# minx_ajh_1_0.net
KiCad netlist of a schematic drawn in EAGLE
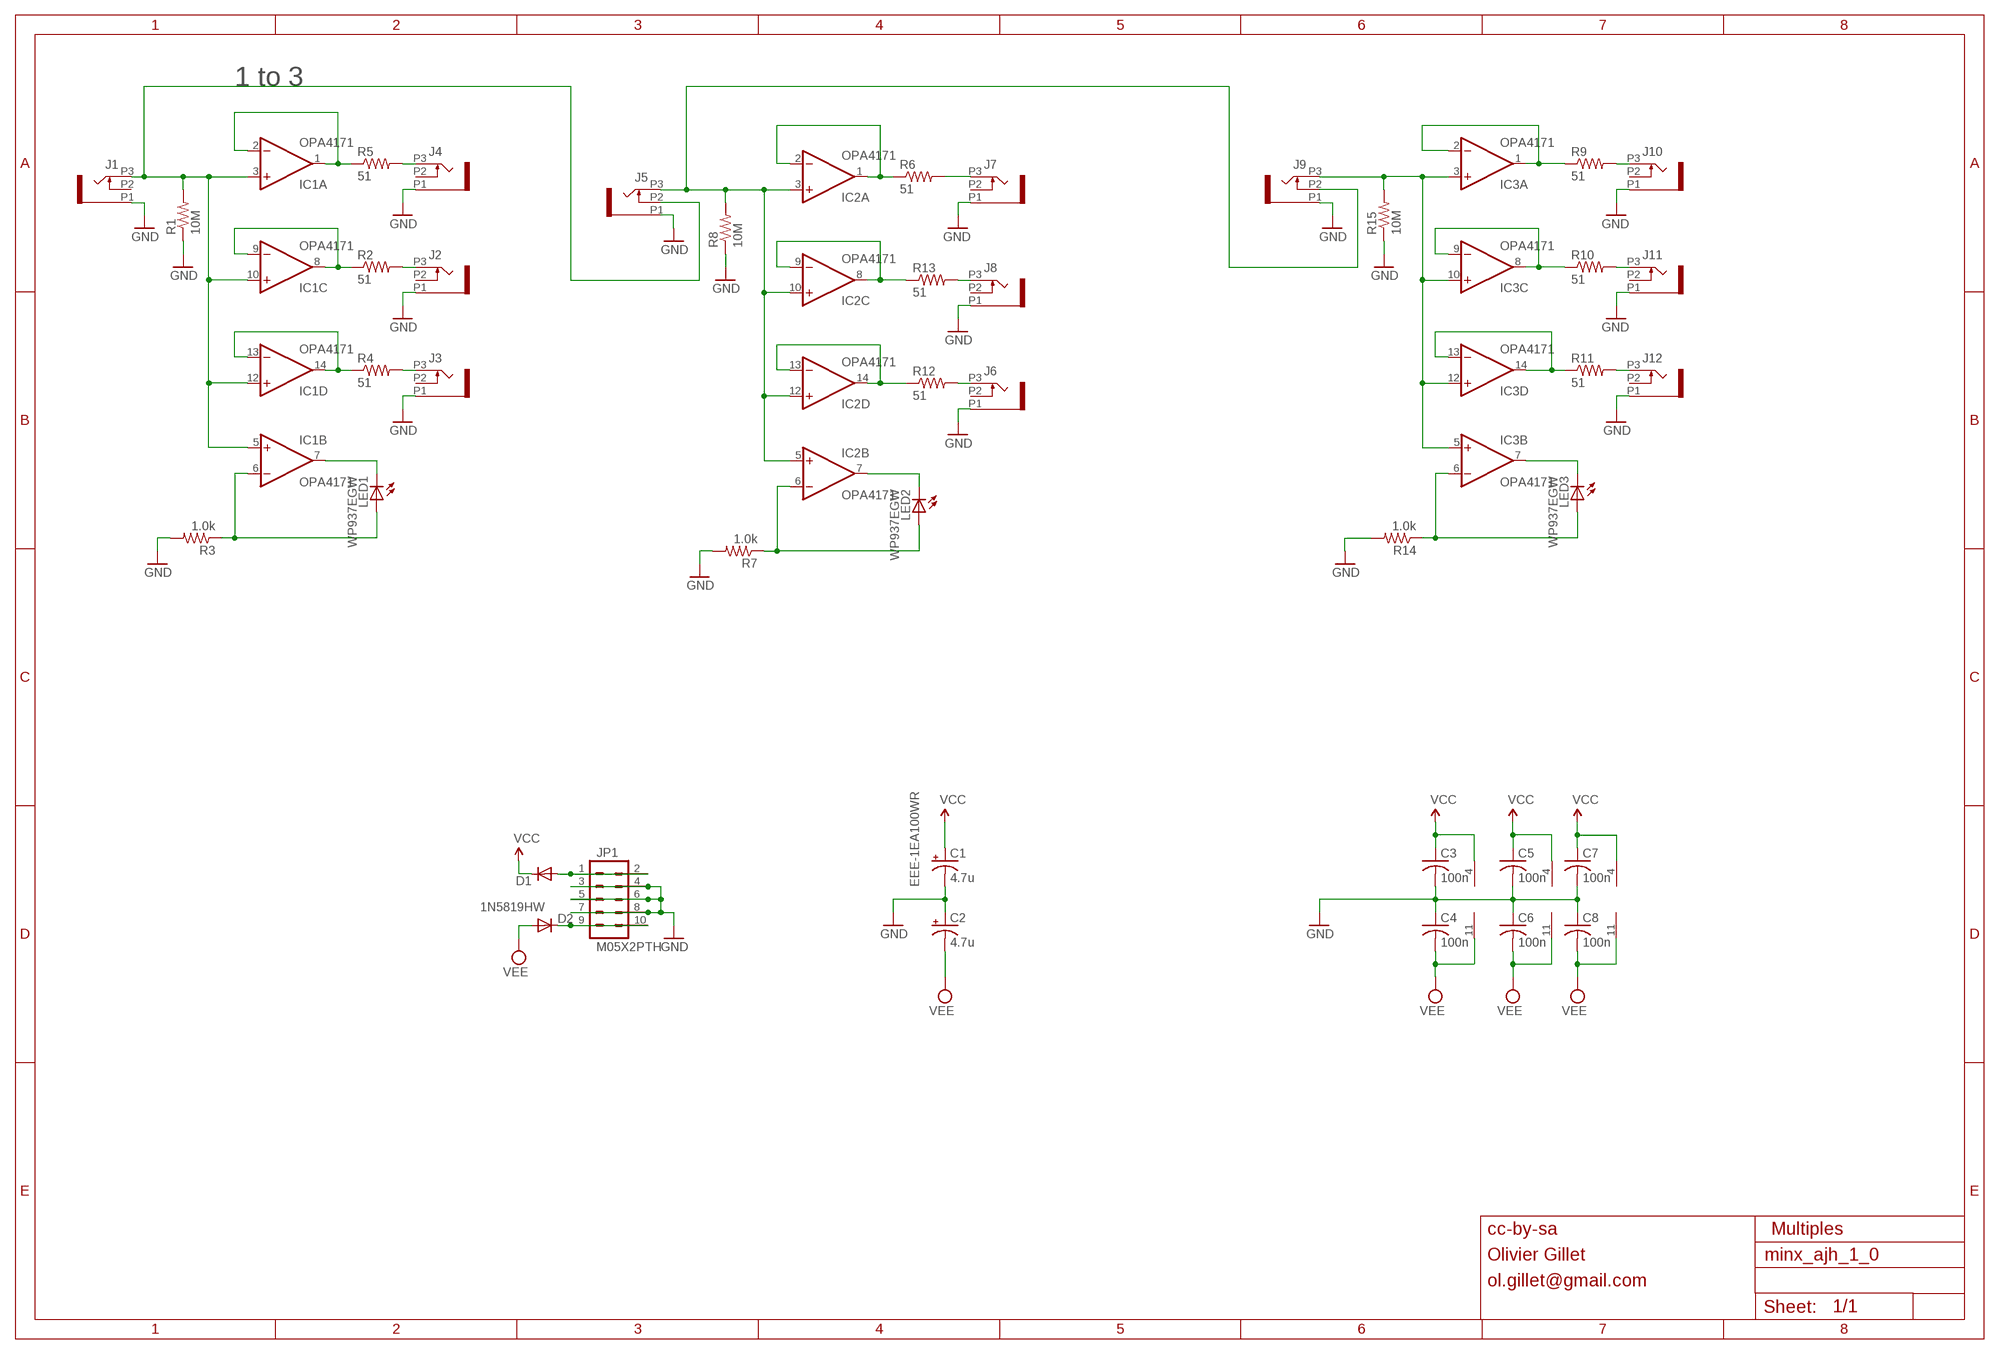
[diagram p0: schematic, sheet 1]

(export (version "E")
  (design (tool "Eeschema 10.0.6"))
  (components
    (comp (ref "C1")
      (value "4.7u")
      (footprint "eagle-import:PANASONIC_A")
      (libsource (lib "eagle-import") (part "CPOL-USA"))
    )
    (comp (ref "C2")
      (value "4.7u")
      (footprint "eagle-import:PANASONIC_A")
      (libsource (lib "eagle-import") (part "CPOL-USA"))
    )
    (comp (ref "C3")
      (value "100n")
      (footprint "eagle-import:C0603")
      (libsource (lib "eagle-import") (part "C-USC0603"))
    )
    (comp (ref "C4")
      (value "100n")
      (footprint "eagle-import:C0603")
      (libsource (lib "eagle-import") (part "C-USC0603"))
    )
    (comp (ref "C5")
      (value "100n")
      (footprint "eagle-import:C0603")
      (libsource (lib "eagle-import") (part "C-USC0603"))
    )
    (comp (ref "C6")
      (value "100n")
      (footprint "eagle-import:C0603")
      (libsource (lib "eagle-import") (part "C-USC0603"))
    )
    (comp (ref "C7")
      (value "100n")
      (footprint "eagle-import:C0603")
      (libsource (lib "eagle-import") (part "C-USC0603"))
    )
    (comp (ref "C8")
      (value "100n")
      (footprint "eagle-import:C0603")
      (libsource (lib "eagle-import") (part "C-USC0603"))
    )
    (comp (ref "D1")
      (value "1N5819HW")
      (footprint "eagle-import:SOD123")
      (libsource (lib "eagle-import") (part "DIODE-SOD123"))
    )
    (comp (ref "D2")
      (value "1N5819HW")
      (footprint "eagle-import:SOD123")
      (libsource (lib "eagle-import") (part "DIODE-SOD123"))
    )
    (comp (ref "IC1")
      (value "OPA4171")
      (footprint "eagle-import:TSSOP14")
      (libsource (lib "eagle-import") (part "TL074PW"))
    )
    (comp (ref "IC2")
      (value "OPA4171")
      (footprint "eagle-import:TSSOP14")
      (libsource (lib "eagle-import") (part "TL074PW"))
    )
    (comp (ref "IC3")
      (value "OPA4171")
      (footprint "eagle-import:TSSOP14")
      (libsource (lib "eagle-import") (part "TL074PW"))
    )
    (comp (ref "J1")
      (value "PJ301_THONKICONN6")
      (footprint "eagle-import:WQP_PJ_301M6")
      (libsource (lib "eagle-import") (part "PJ301_THONKICONN6"))
    )
    (comp (ref "J2")
      (value "PJ301_THONKICONN6")
      (footprint "eagle-import:WQP_PJ_301M6")
      (libsource (lib "eagle-import") (part "PJ301_THONKICONN6"))
    )
    (comp (ref "J3")
      (value "PJ301_THONKICONN6")
      (footprint "eagle-import:WQP_PJ_301M6")
      (libsource (lib "eagle-import") (part "PJ301_THONKICONN6"))
    )
    (comp (ref "J4")
      (value "PJ301_THONKICONN6")
      (footprint "eagle-import:WQP_PJ_301M6")
      (libsource (lib "eagle-import") (part "PJ301_THONKICONN6"))
    )
    (comp (ref "J5")
      (value "PJ301_THONKICONN6")
      (footprint "eagle-import:WQP_PJ_301M6")
      (libsource (lib "eagle-import") (part "PJ301_THONKICONN6"))
    )
    (comp (ref "J6")
      (value "PJ301_THONKICONN6")
      (footprint "eagle-import:WQP_PJ_301M6")
      (libsource (lib "eagle-import") (part "PJ301_THONKICONN6"))
    )
    (comp (ref "J7")
      (value "PJ301_THONKICONN6")
      (footprint "eagle-import:WQP_PJ_301M6")
      (libsource (lib "eagle-import") (part "PJ301_THONKICONN6"))
    )
    (comp (ref "J8")
      (value "PJ301_THONKICONN6")
      (footprint "eagle-import:WQP_PJ_301M6")
      (libsource (lib "eagle-import") (part "PJ301_THONKICONN6"))
    )
    (comp (ref "J9")
      (value "PJ301_THONKICONN6")
      (footprint "eagle-import:WQP_PJ_301M6")
      (libsource (lib "eagle-import") (part "PJ301_THONKICONN6"))
    )
    (comp (ref "J10")
      (value "PJ301_THONKICONN6")
      (footprint "eagle-import:WQP_PJ_301M6")
      (libsource (lib "eagle-import") (part "PJ301_THONKICONN6"))
    )
    (comp (ref "J11")
      (value "PJ301_THONKICONN6")
      (footprint "eagle-import:WQP_PJ_301M6")
      (libsource (lib "eagle-import") (part "PJ301_THONKICONN6"))
    )
    (comp (ref "J12")
      (value "PJ301_THONKICONN6")
      (footprint "eagle-import:WQP_PJ_301M6")
      (libsource (lib "eagle-import") (part "PJ301_THONKICONN6"))
    )
    (comp (ref "JP1")
      (value "M05X2PTH")
      (footprint "eagle-import:AVR_ICSP")
      (libsource (lib "eagle-import") (part "M05X2PTH"))
    )
    (comp (ref "LED1")
      (value "WP937EGW")
      (footprint "eagle-import:LED3MM")
      (libsource (lib "eagle-import") (part "LED3MM"))
    )
    (comp (ref "LED2")
      (value "WP937EGW")
      (footprint "eagle-import:LED3MM")
      (libsource (lib "eagle-import") (part "LED3MM"))
    )
    (comp (ref "LED3")
      (value "WP937EGW")
      (footprint "eagle-import:LED3MM")
      (libsource (lib "eagle-import") (part "LED3MM"))
    )
    (comp (ref "R1")
      (value "10M")
      (footprint "eagle-import:R0603")
      (libsource (lib "eagle-import") (part "R-US_R0603"))
    )
    (comp (ref "R2")
      (value "51")
      (footprint "eagle-import:R0603")
      (libsource (lib "eagle-import") (part "R-US_R0603"))
    )
    (comp (ref "R3")
      (value "1.0k")
      (footprint "eagle-import:R0603")
      (libsource (lib "eagle-import") (part "R-US_R0603"))
    )
    (comp (ref "R4")
      (value "51")
      (footprint "eagle-import:R0603")
      (libsource (lib "eagle-import") (part "R-US_R0603"))
    )
    (comp (ref "R5")
      (value "51")
      (footprint "eagle-import:R0603")
      (libsource (lib "eagle-import") (part "R-US_R0603"))
    )
    (comp (ref "R6")
      (value "51")
      (footprint "eagle-import:R0603")
      (libsource (lib "eagle-import") (part "R-US_R0603"))
    )
    (comp (ref "R7")
      (value "1.0k")
      (footprint "eagle-import:R0603")
      (libsource (lib "eagle-import") (part "R-US_R0603"))
    )
    (comp (ref "R8")
      (value "10M")
      (footprint "eagle-import:R0603")
      (libsource (lib "eagle-import") (part "R-US_R0603"))
    )
    (comp (ref "R9")
      (value "51")
      (footprint "eagle-import:R0603")
      (libsource (lib "eagle-import") (part "R-US_R0603"))
    )
    (comp (ref "R10")
      (value "51")
      (footprint "eagle-import:R0603")
      (libsource (lib "eagle-import") (part "R-US_R0603"))
    )
    (comp (ref "R11")
      (value "51")
      (footprint "eagle-import:R0603")
      (libsource (lib "eagle-import") (part "R-US_R0603"))
    )
    (comp (ref "R12")
      (value "51")
      (footprint "eagle-import:R0603")
      (libsource (lib "eagle-import") (part "R-US_R0603"))
    )
    (comp (ref "R13")
      (value "51")
      (footprint "eagle-import:R0603")
      (libsource (lib "eagle-import") (part "R-US_R0603"))
    )
    (comp (ref "R14")
      (value "1.0k")
      (footprint "eagle-import:R0603")
      (libsource (lib "eagle-import") (part "R-US_R0603"))
    )
    (comp (ref "R15")
      (value "10M")
      (footprint "eagle-import:R0603")
      (libsource (lib "eagle-import") (part "R-US_R0603"))
    )
  )
  (nets
    (net (code "1") (name "GND") (class "Default")
      (node (ref "C1") (pin "-") (pinfunction "-_-") (pintype "passive"))
      (node (ref "C2") (pin "+") (pinfunction "+_+") (pintype "passive"))
      (node (ref "C3") (pin "2") (pinfunction "2_2") (pintype "passive"))
      (node (ref "C4") (pin "1") (pinfunction "1_1") (pintype "passive"))
      (node (ref "C5") (pin "2") (pinfunction "2_2") (pintype "passive"))
      (node (ref "C6") (pin "1") (pinfunction "1_1") (pintype "passive"))
      (node (ref "C7") (pin "2") (pinfunction "2_2") (pintype "passive"))
      (node (ref "C8") (pin "1") (pinfunction "1_1") (pintype "passive"))
      (node (ref "J1") (pin "P1") (pinfunction "1_P1") (pintype "passive"))
      (node (ref "J10") (pin "P1") (pinfunction "1_P1") (pintype "passive"))
      (node (ref "J11") (pin "P1") (pinfunction "1_P1") (pintype "passive"))
      (node (ref "J12") (pin "P1") (pinfunction "1_P1") (pintype "passive"))
      (node (ref "J2") (pin "P1") (pinfunction "1_P1") (pintype "passive"))
      (node (ref "J3") (pin "P1") (pinfunction "1_P1") (pintype "passive"))
      (node (ref "J4") (pin "P1") (pinfunction "1_P1") (pintype "passive"))
      (node (ref "J5") (pin "P1") (pinfunction "1_P1") (pintype "passive"))
      (node (ref "J6") (pin "P1") (pinfunction "1_P1") (pintype "passive"))
      (node (ref "J7") (pin "P1") (pinfunction "1_P1") (pintype "passive"))
      (node (ref "J8") (pin "P1") (pinfunction "1_P1") (pintype "passive"))
      (node (ref "J9") (pin "P1") (pinfunction "1_P1") (pintype "passive"))
      (node (ref "JP1") (pin "3") (pinfunction "3_3") (pintype "passive"))
      (node (ref "JP1") (pin "4") (pinfunction "4_4") (pintype "passive"))
      (node (ref "JP1") (pin "5") (pinfunction "5_5") (pintype "passive"))
      (node (ref "JP1") (pin "6") (pinfunction "6_6") (pintype "passive"))
      (node (ref "JP1") (pin "7") (pinfunction "7_7") (pintype "passive"))
      (node (ref "JP1") (pin "8") (pinfunction "8_8") (pintype "passive"))
      (node (ref "R1") (pin "1") (pinfunction "1_1") (pintype "passive"))
      (node (ref "R14") (pin "2") (pinfunction "2_2") (pintype "passive"))
      (node (ref "R15") (pin "1") (pinfunction "1_1") (pintype "passive"))
      (node (ref "R3") (pin "2") (pinfunction "2_2") (pintype "passive"))
      (node (ref "R7") (pin "2") (pinfunction "2_2") (pintype "passive"))
      (node (ref "R8") (pin "1") (pinfunction "1_1") (pintype "passive"))
    )
    (net (code "2") (name "Net-(D1-PadA)") (class "Default")
      (node (ref "D1") (pin "A") (pinfunction "A_A") (pintype "passive"))
      (node (ref "JP1") (pin "1") (pinfunction "1_1") (pintype "passive"))
      (node (ref "JP1") (pin "2") (pinfunction "2_2") (pintype "passive"))
    )
    (net (code "3") (name "Net-(D2-PadC)") (class "Default")
      (node (ref "D2") (pin "C") (pinfunction "C_C") (pintype "passive"))
      (node (ref "JP1") (pin "10") (pinfunction "10_10") (pintype "passive"))
      (node (ref "JP1") (pin "9") (pinfunction "9_9") (pintype "passive"))
    )
    (net (code "4") (name "Net-(IC1A-+IN)") (class "Default")
      (node (ref "IC1") (pin "10") (pinfunction "+IN_10") (pintype "input"))
      (node (ref "IC1") (pin "12") (pinfunction "+IN_12") (pintype "input"))
      (node (ref "IC1") (pin "3") (pinfunction "+IN_3") (pintype "input"))
      (node (ref "IC1") (pin "5") (pinfunction "+IN_5") (pintype "input"))
      (node (ref "J1") (pin "P3") (pinfunction "3_P3") (pintype "passive"))
      (node (ref "J5") (pin "P2") (pinfunction "2_P2") (pintype "passive"))
      (node (ref "R1") (pin "2") (pinfunction "2_2") (pintype "passive"))
    )
    (net (code "5") (name "Net-(IC1A--IN)") (class "Default")
      (node (ref "IC1") (pin "1") (pinfunction "OUT_1") (pintype "output"))
      (node (ref "IC1") (pin "2") (pinfunction "-IN_2") (pintype "input"))
      (node (ref "R5") (pin "1") (pinfunction "1_1") (pintype "passive"))
    )
    (net (code "6") (name "Net-(IC1B--IN)") (class "Default")
      (node (ref "IC1") (pin "6") (pinfunction "-IN_6") (pintype "input"))
      (node (ref "LED1") (pin "A") (pinfunction "A_A") (pintype "passive"))
      (node (ref "R3") (pin "1") (pinfunction "1_1") (pintype "passive"))
    )
    (net (code "7") (name "Net-(IC1B-OUT)") (class "Default")
      (node (ref "IC1") (pin "7") (pinfunction "OUT_7") (pintype "output"))
      (node (ref "LED1") (pin "K") (pinfunction "C_K") (pintype "passive"))
    )
    (net (code "8") (name "Net-(IC1C--IN)") (class "Default")
      (node (ref "IC1") (pin "8") (pinfunction "OUT_8") (pintype "output"))
      (node (ref "IC1") (pin "9") (pinfunction "-IN_9") (pintype "input"))
      (node (ref "R2") (pin "1") (pinfunction "1_1") (pintype "passive"))
    )
    (net (code "9") (name "Net-(IC1D--IN)") (class "Default")
      (node (ref "IC1") (pin "13") (pinfunction "-IN_13") (pintype "input"))
      (node (ref "IC1") (pin "14") (pinfunction "OUT_14") (pintype "output"))
      (node (ref "R4") (pin "1") (pinfunction "1_1") (pintype "passive"))
    )
    (net (code "10") (name "Net-(IC2A-+IN)") (class "Default")
      (node (ref "IC2") (pin "10") (pinfunction "+IN_10") (pintype "input"))
      (node (ref "IC2") (pin "12") (pinfunction "+IN_12") (pintype "input"))
      (node (ref "IC2") (pin "3") (pinfunction "+IN_3") (pintype "input"))
      (node (ref "IC2") (pin "5") (pinfunction "+IN_5") (pintype "input"))
      (node (ref "J5") (pin "P3") (pinfunction "3_P3") (pintype "passive"))
      (node (ref "J9") (pin "P2") (pinfunction "2_P2") (pintype "passive"))
      (node (ref "R8") (pin "2") (pinfunction "2_2") (pintype "passive"))
    )
    (net (code "11") (name "Net-(IC2A--IN)") (class "Default")
      (node (ref "IC2") (pin "1") (pinfunction "OUT_1") (pintype "output"))
      (node (ref "IC2") (pin "2") (pinfunction "-IN_2") (pintype "input"))
      (node (ref "R6") (pin "1") (pinfunction "1_1") (pintype "passive"))
    )
    (net (code "12") (name "Net-(IC2B--IN)") (class "Default")
      (node (ref "IC2") (pin "6") (pinfunction "-IN_6") (pintype "input"))
      (node (ref "LED2") (pin "A") (pinfunction "A_A") (pintype "passive"))
      (node (ref "R7") (pin "1") (pinfunction "1_1") (pintype "passive"))
    )
    (net (code "13") (name "Net-(IC2B-OUT)") (class "Default")
      (node (ref "IC2") (pin "7") (pinfunction "OUT_7") (pintype "output"))
      (node (ref "LED2") (pin "K") (pinfunction "C_K") (pintype "passive"))
    )
    (net (code "14") (name "Net-(IC2C--IN)") (class "Default")
      (node (ref "IC2") (pin "8") (pinfunction "OUT_8") (pintype "output"))
      (node (ref "IC2") (pin "9") (pinfunction "-IN_9") (pintype "input"))
      (node (ref "R13") (pin "1") (pinfunction "1_1") (pintype "passive"))
    )
    (net (code "15") (name "Net-(IC2D--IN)") (class "Default")
      (node (ref "IC2") (pin "13") (pinfunction "-IN_13") (pintype "input"))
      (node (ref "IC2") (pin "14") (pinfunction "OUT_14") (pintype "output"))
      (node (ref "R12") (pin "1") (pinfunction "1_1") (pintype "passive"))
    )
    (net (code "16") (name "Net-(IC3A-+IN)") (class "Default")
      (node (ref "IC3") (pin "10") (pinfunction "+IN_10") (pintype "input"))
      (node (ref "IC3") (pin "12") (pinfunction "+IN_12") (pintype "input"))
      (node (ref "IC3") (pin "3") (pinfunction "+IN_3") (pintype "input"))
      (node (ref "IC3") (pin "5") (pinfunction "+IN_5") (pintype "input"))
      (node (ref "J9") (pin "P3") (pinfunction "3_P3") (pintype "passive"))
      (node (ref "R15") (pin "2") (pinfunction "2_2") (pintype "passive"))
    )
    (net (code "17") (name "Net-(IC3A--IN)") (class "Default")
      (node (ref "IC3") (pin "1") (pinfunction "OUT_1") (pintype "output"))
      (node (ref "IC3") (pin "2") (pinfunction "-IN_2") (pintype "input"))
      (node (ref "R9") (pin "1") (pinfunction "1_1") (pintype "passive"))
    )
    (net (code "18") (name "Net-(IC3B--IN)") (class "Default")
      (node (ref "IC3") (pin "6") (pinfunction "-IN_6") (pintype "input"))
      (node (ref "LED3") (pin "A") (pinfunction "A_A") (pintype "passive"))
      (node (ref "R14") (pin "1") (pinfunction "1_1") (pintype "passive"))
    )
    (net (code "19") (name "Net-(IC3B-OUT)") (class "Default")
      (node (ref "IC3") (pin "7") (pinfunction "OUT_7") (pintype "output"))
      (node (ref "LED3") (pin "K") (pinfunction "C_K") (pintype "passive"))
    )
    (net (code "20") (name "Net-(IC3C--IN)") (class "Default")
      (node (ref "IC3") (pin "8") (pinfunction "OUT_8") (pintype "output"))
      (node (ref "IC3") (pin "9") (pinfunction "-IN_9") (pintype "input"))
      (node (ref "R10") (pin "1") (pinfunction "1_1") (pintype "passive"))
    )
    (net (code "21") (name "Net-(IC3D--IN)") (class "Default")
      (node (ref "IC3") (pin "13") (pinfunction "-IN_13") (pintype "input"))
      (node (ref "IC3") (pin "14") (pinfunction "OUT_14") (pintype "output"))
      (node (ref "R11") (pin "1") (pinfunction "1_1") (pintype "passive"))
    )
    (net (code "22") (name "Net-(J2-3)") (class "Default")
      (node (ref "J2") (pin "P3") (pinfunction "3_P3") (pintype "passive"))
      (node (ref "R2") (pin "2") (pinfunction "2_2") (pintype "passive"))
    )
    (net (code "23") (name "Net-(J3-3)") (class "Default")
      (node (ref "J3") (pin "P3") (pinfunction "3_P3") (pintype "passive"))
      (node (ref "R4") (pin "2") (pinfunction "2_2") (pintype "passive"))
    )
    (net (code "24") (name "Net-(J4-3)") (class "Default")
      (node (ref "J4") (pin "P3") (pinfunction "3_P3") (pintype "passive"))
      (node (ref "R5") (pin "2") (pinfunction "2_2") (pintype "passive"))
    )
    (net (code "25") (name "Net-(J6-3)") (class "Default")
      (node (ref "J6") (pin "P3") (pinfunction "3_P3") (pintype "passive"))
      (node (ref "R12") (pin "2") (pinfunction "2_2") (pintype "passive"))
    )
    (net (code "26") (name "Net-(J7-3)") (class "Default")
      (node (ref "J7") (pin "P3") (pinfunction "3_P3") (pintype "passive"))
      (node (ref "R6") (pin "2") (pinfunction "2_2") (pintype "passive"))
    )
    (net (code "27") (name "Net-(J8-3)") (class "Default")
      (node (ref "J8") (pin "P3") (pinfunction "3_P3") (pintype "passive"))
      (node (ref "R13") (pin "2") (pinfunction "2_2") (pintype "passive"))
    )
    (net (code "28") (name "Net-(J10-3)") (class "Default")
      (node (ref "J10") (pin "P3") (pinfunction "3_P3") (pintype "passive"))
      (node (ref "R9") (pin "2") (pinfunction "2_2") (pintype "passive"))
    )
    (net (code "29") (name "Net-(J11-3)") (class "Default")
      (node (ref "J11") (pin "P3") (pinfunction "3_P3") (pintype "passive"))
      (node (ref "R10") (pin "2") (pinfunction "2_2") (pintype "passive"))
    )
    (net (code "30") (name "Net-(J12-3)") (class "Default")
      (node (ref "J12") (pin "P3") (pinfunction "3_P3") (pintype "passive"))
      (node (ref "R11") (pin "2") (pinfunction "2_2") (pintype "passive"))
    )
    (net (code "31") (name "VCC") (class "Default")
      (node (ref "C1") (pin "+") (pinfunction "+_+") (pintype "passive"))
      (node (ref "C3") (pin "1") (pinfunction "1_1") (pintype "passive"))
      (node (ref "C5") (pin "1") (pinfunction "1_1") (pintype "passive"))
      (node (ref "C7") (pin "1") (pinfunction "1_1") (pintype "passive"))
      (node (ref "D1") (pin "C") (pinfunction "C_C") (pintype "passive"))
      (node (ref "IC1") (pin "4") (pinfunction "V+_4") (pintype "power_in"))
      (node (ref "IC2") (pin "4") (pinfunction "V+_4") (pintype "power_in"))
      (node (ref "IC3") (pin "4") (pinfunction "V+_4") (pintype "power_in"))
    )
    (net (code "32") (name "VEE") (class "Default")
      (node (ref "C2") (pin "-") (pinfunction "-_-") (pintype "passive"))
      (node (ref "C4") (pin "2") (pinfunction "2_2") (pintype "passive"))
      (node (ref "C6") (pin "2") (pinfunction "2_2") (pintype "passive"))
      (node (ref "C8") (pin "2") (pinfunction "2_2") (pintype "passive"))
      (node (ref "D2") (pin "A") (pinfunction "A_A") (pintype "passive"))
      (node (ref "IC1") (pin "11") (pinfunction "V-_11") (pintype "power_in"))
      (node (ref "IC2") (pin "11") (pinfunction "V-_11") (pintype "power_in"))
      (node (ref "IC3") (pin "11") (pinfunction "V-_11") (pintype "power_in"))
    )
    (net (code "33") (name "unconnected-(J1-2-PadP2)") (class "Default")
      (node (ref "J1") (pin "P2") (pinfunction "2_P2") (pintype "passive"))
    )
    (net (code "34") (name "unconnected-(J2-2-PadP2)") (class "Default")
      (node (ref "J2") (pin "P2") (pinfunction "2_P2") (pintype "passive"))
    )
    (net (code "35") (name "unconnected-(J3-2-PadP2)") (class "Default")
      (node (ref "J3") (pin "P2") (pinfunction "2_P2") (pintype "passive"))
    )
    (net (code "36") (name "unconnected-(J4-2-PadP2)") (class "Default")
      (node (ref "J4") (pin "P2") (pinfunction "2_P2") (pintype "passive"))
    )
    (net (code "37") (name "unconnected-(J6-2-PadP2)") (class "Default")
      (node (ref "J6") (pin "P2") (pinfunction "2_P2") (pintype "passive"))
    )
    (net (code "38") (name "unconnected-(J7-2-PadP2)") (class "Default")
      (node (ref "J7") (pin "P2") (pinfunction "2_P2") (pintype "passive"))
    )
    (net (code "39") (name "unconnected-(J8-2-PadP2)") (class "Default")
      (node (ref "J8") (pin "P2") (pinfunction "2_P2") (pintype "passive"))
    )
    (net (code "40") (name "unconnected-(J10-2-PadP2)") (class "Default")
      (node (ref "J10") (pin "P2") (pinfunction "2_P2") (pintype "passive"))
    )
    (net (code "41") (name "unconnected-(J11-2-PadP2)") (class "Default")
      (node (ref "J11") (pin "P2") (pinfunction "2_P2") (pintype "passive"))
    )
    (net (code "42") (name "unconnected-(J12-2-PadP2)") (class "Default")
      (node (ref "J12") (pin "P2") (pinfunction "2_P2") (pintype "passive"))
    )
  )
)
